# AC_DC_POWER.net
KiCad netlist of a schematic drawn in Altium Designer
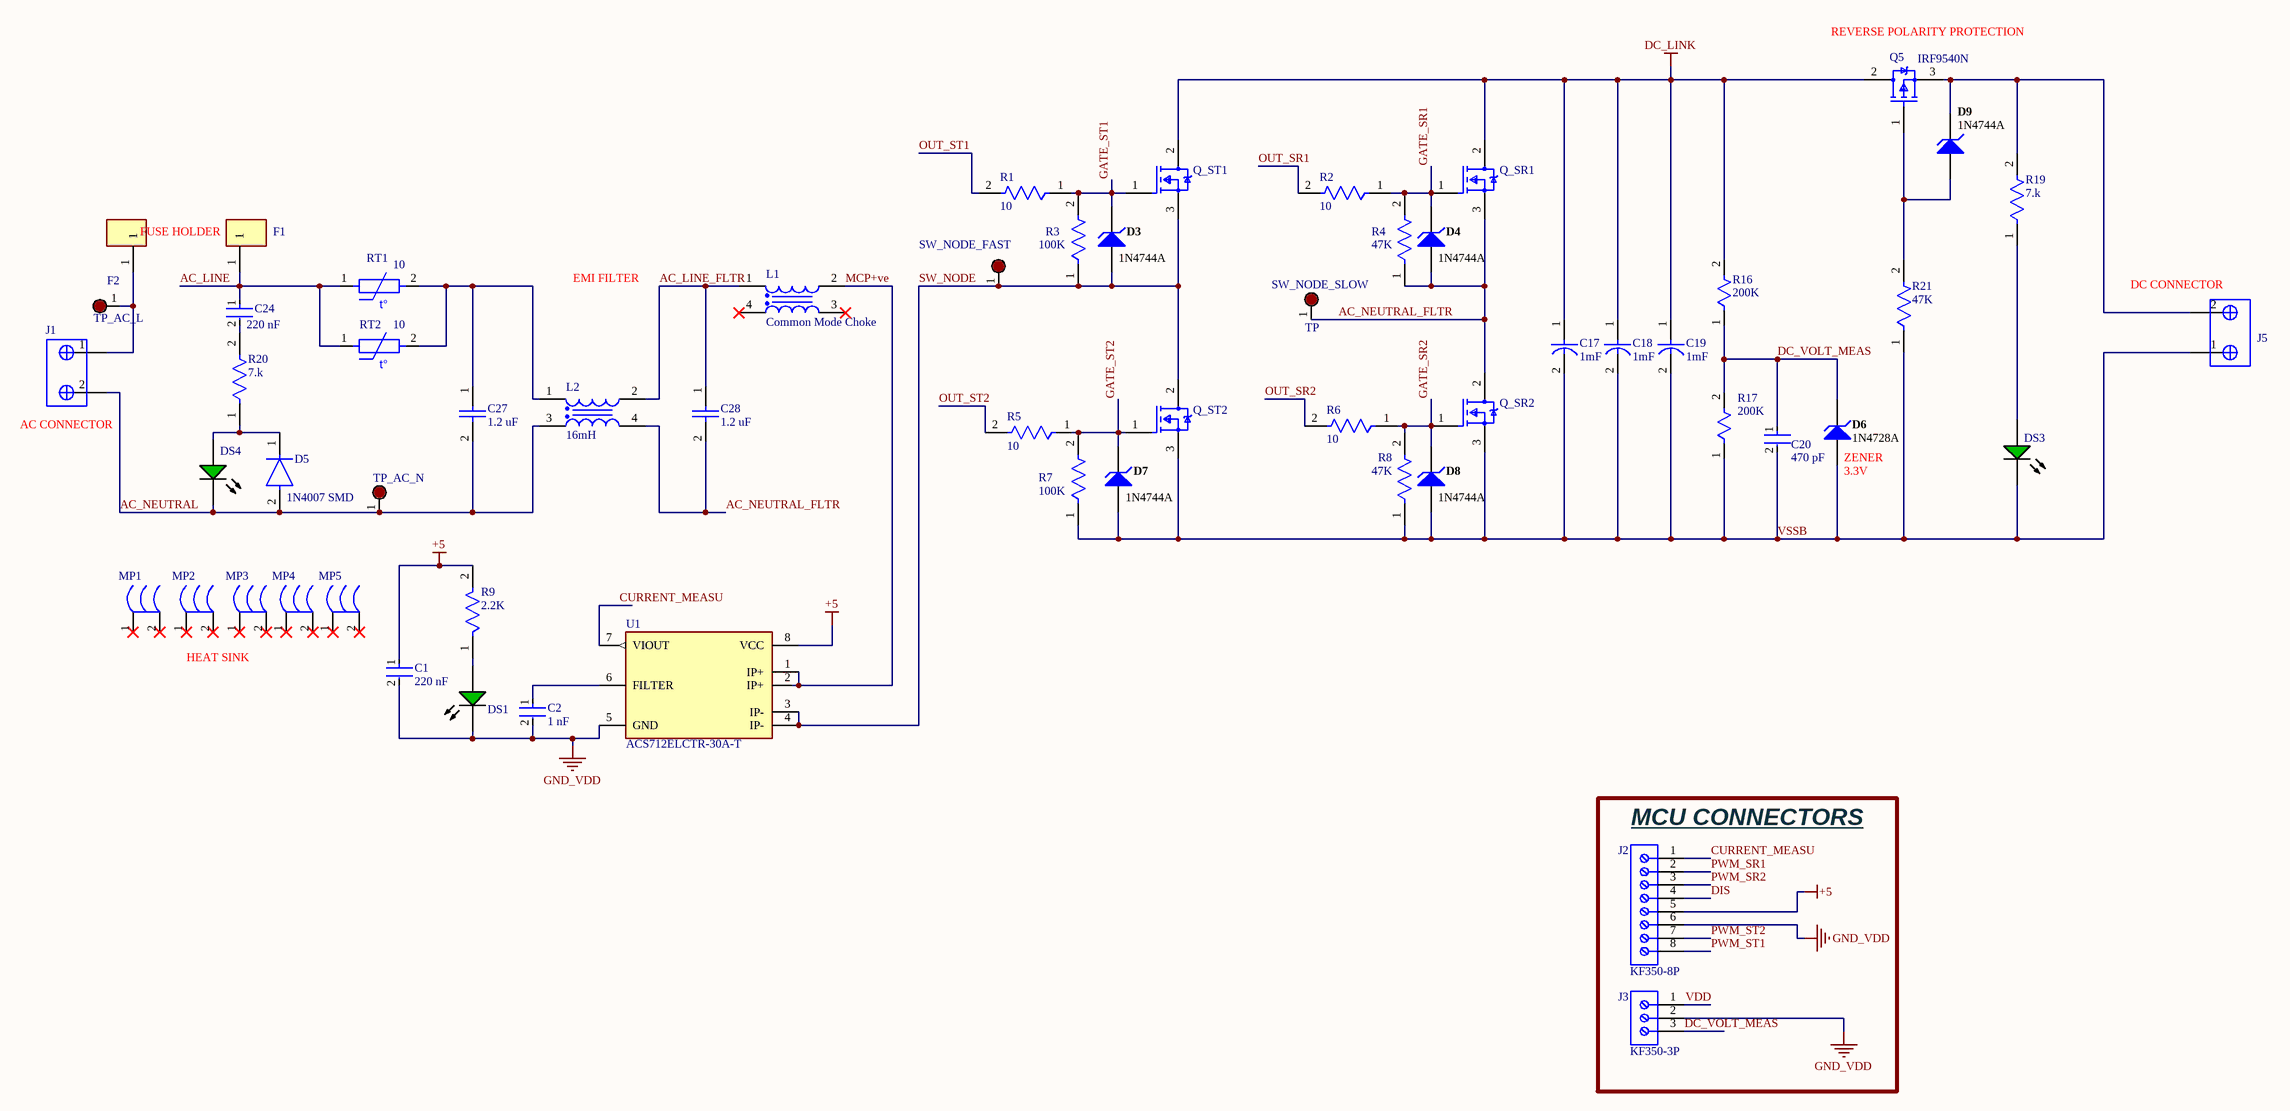
[diagram p0: AC_DC_POWER.SchDoc]

(export (version "E")
  (design (tool "Eeschema 10.0.6"))
  (components
    (comp (ref "C1")
      (value "220 nF")
      (footprint "FP-C0805C-DN-MFG")
      (description "CAP CER 0.22UF 50V X7R 0805")
      (fields
        (field (name "MANUFACTURER") "KEMET")
        (field (name "OCTOPART") "https://octopart.com/c0805c224k5ractu-kemet-144670")
      )
      (libsource (lib "Altium Content Vault") (part "b4654b650e69147ec39a6b967a45e02"))
    )
    (comp (ref "C2")
      (value "1 nF")
      (footprint "FP-C0805C-DN-MFG")
      (description "CAP CER 0.22UF 50V X7R 0805")
      (fields
        (field (name "MANUFACTURER") "KEMET")
        (field (name "OCTOPART") "https://octopart.com/c0805c224k5ractu-kemet-144670")
      )
      (libsource (lib "Altium Content Vault") (part "b4654b650e69147ec39a6b967a45e02"))
    )
    (comp (ref "C17")
      (value "1mF")
      (footprint "PCBComponent_1")
      (libsource (lib "CD293H Capacitor") (part "C"))
    )
    (comp (ref "C18")
      (value "1mF")
      (footprint "PCBComponent_1")
      (libsource (lib "CD293H Capacitor") (part "C"))
    )
    (comp (ref "C19")
      (value "1mF")
      (footprint "PCBComponent_1")
      (libsource (lib "CD293H Capacitor") (part "C"))
    )
    (comp (ref "C20")
      (value "470 pF")
      (footprint "FP-C0805C-DN-MFG")
      (description "CAP CER 0.22UF 50V X7R 0805")
      (fields
        (field (name "MANUFACTURER") "KEMET")
        (field (name "OCTOPART") "https://octopart.com/c0805c224k5ractu-kemet-144670")
      )
      (libsource (lib "Altium Content Vault") (part "b4654b650e69147ec39a6b967a45e02"))
    )
    (comp (ref "C24")
      (value "220 nF")
      (footprint "FP-C0805C-DN-MFG")
      (description "CAP CER 0.22UF 50V X7R 0805")
      (fields
        (field (name "MANUFACTURER") "KEMET")
        (field (name "OCTOPART") "https://octopart.com/c0805c224k5ractu-kemet-144670")
      )
      (libsource (lib "Altium Content Vault") (part "b4654b650e69147ec39a6b967a45e02"))
    )
    (comp (ref "C27")
      (value "1.2 uF")
      (footprint "PCBComponent_1")
      (description "H124K \r\n450MPPN")
      (libsource (lib "H124K Film Capacitor") (part "H124K"))
    )
    (comp (ref "C28")
      (value "1.2 uF")
      (footprint "PCBComponent_1")
      (description "H124K \r\n450MPPN")
      (libsource (lib "H124K Film Capacitor") (part "H124K"))
    )
    (comp (ref "D3")
      (value "1N4744A")
      (footprint "FAIR-DO-41-2_V")
      (description "Zener Diode, 15V, 1W, 5%, -65 to 200 degC, 2-Pin DO-41, Body 2.72 x 5.2 mm, RoHS")
      (fields (field (name "MANUFACTURER") "Fairchild Semiconductor") (field (name "TOLERANCE") "5%"))
      (libsource (lib "Altium Content Vault") (part "FAIR-DZEN-A1K2-2"))
    )
    (comp (ref "D4")
      (value "1N4744A")
      (footprint "FAIR-DO-41-2_V")
      (description "Zener Diode, 15V, 1W, 5%, -65 to 200 degC, 2-Pin DO-41, Body 2.72 x 5.2 mm, RoHS")
      (fields (field (name "MANUFACTURER") "Fairchild Semiconductor") (field (name "TOLERANCE") "5%"))
      (libsource (lib "Altium Content Vault") (part "FAIR-DZEN-A1K2-2"))
    )
    (comp (ref "D5")
      (value "1N4007 SMD")
      (footprint "FP-1N4007_SMD-IPC_C")
      (description "Rectifier, 1Kv, 1A, Do-214Ac Rohs Compliant: Yes")
      (libsource (lib "Altium Content Vault") (part "d7152d700b627762746794eb795d46e"))
    )
    (comp (ref "D6")
      (value "1N4728A")
      (footprint "FAIR-DO-41-2_V")
      (description "Zener Diode, 3.3V, 1W, 5%, -65 to 200 degC, 2-Pin DO-41, Body 2.72 x 5.2 mm, RoHS")
      (fields (field (name "MANUFACTURER") "Fairchild Semiconductor") (field (name "TOLERANCE") "5%"))
      (libsource (lib "Altium Content Vault") (part "FAIR-DZEN-A1K2-2"))
    )
    (comp (ref "D7")
      (value "1N4744A")
      (footprint "FAIR-DO-41-2_V")
      (description "Zener Diode, 15V, 1W, 5%, -65 to 200 degC, 2-Pin DO-41, Body 2.72 x 5.2 mm, RoHS")
      (fields (field (name "MANUFACTURER") "Fairchild Semiconductor") (field (name "TOLERANCE") "5%"))
      (libsource (lib "Altium Content Vault") (part "FAIR-DZEN-A1K2-2"))
    )
    (comp (ref "D8")
      (value "1N4744A")
      (footprint "FAIR-DO-41-2_V")
      (description "Zener Diode, 15V, 1W, 5%, -65 to 200 degC, 2-Pin DO-41, Body 2.72 x 5.2 mm, RoHS")
      (fields (field (name "MANUFACTURER") "Fairchild Semiconductor") (field (name "TOLERANCE") "5%"))
      (libsource (lib "Altium Content Vault") (part "FAIR-DZEN-A1K2-2"))
    )
    (comp (ref "D9")
      (value "1N4744A")
      (footprint "FAIR-DO-41-2_V")
      (description "Zener Diode, 15V, 1W, 5%, -65 to 200 degC, 2-Pin DO-41, Body 2.72 x 5.2 mm, RoHS")
      (fields (field (name "MANUFACTURER") "Fairchild Semiconductor") (field (name "TOLERANCE") "5%"))
      (libsource (lib "Altium Content Vault") (part "FAIR-DZEN-A1K2-2"))
    )
    (comp (ref "DS1")
      (value "HSMG-C170")
      (footprint "AVAG-HSMX-C170_V")
      (description "Chip LED, Green, 2.2 V, -40 to 85 degC, 2-Pin SMD, Pb-Free, Tape and Reel")
      (fields (field (name "MANUFACTURER") "Avago"))
      (libsource (lib "Altium Content Vault") (part "LED_GREEN_A1K2-2"))
    )
    (comp (ref "DS3")
      (value "HSMG-C170")
      (footprint "AVAG-HSMX-C170_V")
      (description "Chip LED, Green, 2.2 V, -40 to 85 degC, 2-Pin SMD, Pb-Free, Tape and Reel")
      (fields (field (name "MANUFACTURER") "Avago"))
      (libsource (lib "Altium Content Vault") (part "LED_GREEN_A1K2-2"))
    )
    (comp (ref "DS4")
      (value "HSMG-C170")
      (footprint "AVAG-HSMX-C170_V")
      (description "Chip LED, Green, 2.2 V, -40 to 85 degC, 2-Pin SMD, Pb-Free, Tape and Reel")
      (fields (field (name "MANUFACTURER") "Avago"))
      (libsource (lib "Altium Content Vault") (part "LED_GREEN_A1K2-2"))
    )
    (comp (ref "F1")
      (value "0751.0110")
      (footprint "FP-0751_0110-MFG")
      (description "FUSE CLIP CARTRIDGE 10A PCB")
      (fields
        (field (name "OCTOPART") "https://octopart.com/0751.0110-schurter-19402")
        (field (name "MANUFACTURER") "Schurter")
      )
      (libsource (lib "") (part "6594cd1380bf084bed0a40489f8b218_1"))
    )
    (comp (ref "F2")
      (value "0751.0110")
      (footprint "FP-0751_0110-MFG")
      (description "FUSE CLIP CARTRIDGE 10A PCB")
      (fields
        (field (name "OCTOPART") "https://octopart.com/0751.0110-schurter-19402")
        (field (name "MANUFACTURER") "Schurter")
      )
      (libsource (lib "Altium Content Vault") (part "6594cd1380bf084bed0a40489f8b218"))
    )
    (comp (ref "J1")
      (value "Barrier_2_pins")
      (footprint "PCBComponent_1")
      (libsource (lib "Barrier Terminal 9.5mm 2-Pins") (part "Barrier_2_pins"))
    )
    (comp (ref "J2")
      (value "KF350-8P")
      (footprint "PCBComponent_1")
      (libsource (lib "KF350-3.5mm-8P") (part "KF350-8P"))
    )
    (comp (ref "J3")
      (value "KF350-3P")
      (footprint "PCBComponent_1")
      (libsource (lib "KF350-3P") (part "KF350-3P"))
    )
    (comp (ref "J5")
      (value "Barrier_2_pins")
      (footprint "PCBComponent_1")
      (libsource (lib "Barrier Terminal 9.5mm 2-Pins") (part "Barrier_2_pins"))
    )
    (comp (ref "L1")
      (value "Common Mode Choke")
      (footprint "PCBComponent_1")
      (libsource (lib "R6123-X425_Choke") (part "T60405-R6123-X425"))
    )
    (comp (ref "L2")
      (value "16mH")
      (footprint "PCBComponent_1")
      (description "Common Mode Choke\r\nEach Coil inductance = 16mH")
      (libsource (lib "Common Mode Choke") (part "Choke"))
    )
    (comp (ref "MP1")
      (value "Heat Sink")
      (footprint "PCBComponent_1")
      (libsource (lib "Heat Sink 34_12_25") (part "Heat Sink"))
    )
    (comp (ref "MP2")
      (value "Heat Sink")
      (footprint "PCBComponent_1")
      (libsource (lib "Heat Sink 34_12_25") (part "Heat Sink"))
    )
    (comp (ref "MP3")
      (value "Heat Sink")
      (footprint "PCBComponent_1")
      (libsource (lib "Heat Sink 34_12_25") (part "Heat Sink"))
    )
    (comp (ref "MP4")
      (value "Heat Sink")
      (footprint "PCBComponent_1")
      (libsource (lib "Heat Sink 34_12_25") (part "Heat Sink"))
    )
    (comp (ref "MP5")
      (value "Heat Sink")
      (footprint "PCBComponent_1")
      (libsource (lib "Heat Sink 34_12_25") (part "Heat Sink"))
    )
    (comp (ref "Q5")
      (value "IRF9540N")
      (footprint "PCBComponent_1")
      (libsource (lib "IRF9540N") (part "IRF9540N"))
    )
    (comp (ref "Q_SR1")
      (value "IRFP4227PBF")
      (footprint "FP-PG-TO247-3-MFG")
      (description "MOSFET N-CH 200V 65A TO247AC")
      (libsource (lib "Altium Content Vault") (part "8b62d417cbef8344eebe0bde0c45977"))
    )
    (comp (ref "Q_SR2")
      (value "IRFP4227PBF")
      (footprint "FP-PG-TO247-3-MFG")
      (description "MOSFET N-CH 200V 65A TO247AC")
      (libsource (lib "Altium Content Vault") (part "8b62d417cbef8344eebe0bde0c45977"))
    )
    (comp (ref "Q_ST1")
      (value "IRFP4227PBF")
      (footprint "FP-PG-TO247-3-MFG")
      (description "MOSFET N-CH 200V 65A TO247AC")
      (libsource (lib "Altium Content Vault") (part "8b62d417cbef8344eebe0bde0c45977"))
    )
    (comp (ref "Q_ST2")
      (value "IRFP4227PBF")
      (footprint "FP-PG-TO247-3-MFG")
      (description "MOSFET N-CH 200V 65A TO247AC")
      (libsource (lib "Altium Content Vault") (part "8b62d417cbef8344eebe0bde0c45977"))
    )
    (comp (ref "R1")
      (value "10")
      (footprint "FP-RC0805-0_6-IPC_C")
      (description "RES 100K OHM 1% 1/8W 0805")
      (fields (field (name "TOLERANCE") "1%"))
      (libsource (lib "Altium Content Vault") (part "1029c3af85768c4190bb7ad29bc67b5"))
    )
    (comp (ref "R2")
      (value "10")
      (footprint "FP-RC0805-0_6-IPC_C")
      (description "RES 100K OHM 1% 1/8W 0805")
      (fields (field (name "TOLERANCE") "1%"))
      (libsource (lib "Altium Content Vault") (part "1029c3af85768c4190bb7ad29bc67b5"))
    )
    (comp (ref "R3")
      (value "100K")
      (footprint "FP-RC0805-0_6-IPC_C")
      (description "RES 100K OHM 1% 1/8W 0805")
      (fields (field (name "TOLERANCE") "1%"))
      (libsource (lib "Altium Content Vault") (part "1029c3af85768c4190bb7ad29bc67b5"))
    )
    (comp (ref "R4")
      (value "47K")
      (footprint "FP-RC0805-0_6-IPC_C")
      (description "RES 100K OHM 1% 1/8W 0805")
      (fields (field (name "TOLERANCE") "1%"))
      (libsource (lib "Altium Content Vault") (part "1029c3af85768c4190bb7ad29bc67b5"))
    )
    (comp (ref "R5")
      (value "10")
      (footprint "FP-RC0805-0_6-IPC_C")
      (description "RES 100K OHM 1% 1/8W 0805")
      (fields (field (name "TOLERANCE") "1%"))
      (libsource (lib "Altium Content Vault") (part "1029c3af85768c4190bb7ad29bc67b5"))
    )
    (comp (ref "R6")
      (value "10")
      (footprint "FP-RC0805-0_6-IPC_C")
      (description "RES 100K OHM 1% 1/8W 0805")
      (fields (field (name "TOLERANCE") "1%"))
      (libsource (lib "Altium Content Vault") (part "1029c3af85768c4190bb7ad29bc67b5"))
    )
    (comp (ref "R7")
      (value "100K")
      (footprint "FP-RC0805-0_6-IPC_C")
      (description "RES 100K OHM 1% 1/8W 0805")
      (fields (field (name "TOLERANCE") "1%"))
      (libsource (lib "Altium Content Vault") (part "1029c3af85768c4190bb7ad29bc67b5"))
    )
    (comp (ref "R8")
      (value "47K")
      (footprint "FP-RC0805-0_6-IPC_C")
      (description "RES 100K OHM 1% 1/8W 0805")
      (fields (field (name "TOLERANCE") "1%"))
      (libsource (lib "Altium Content Vault") (part "1029c3af85768c4190bb7ad29bc67b5"))
    )
    (comp (ref "R9")
      (value "2.2K")
      (footprint "FP-RC0805-0_6-IPC_C")
      (description "RES 100K OHM 1% 1/8W 0805")
      (fields (field (name "TOLERANCE") "1%"))
      (libsource (lib "Altium Content Vault") (part "1029c3af85768c4190bb7ad29bc67b5"))
    )
    (comp (ref "R16")
      (value "200K")
      (footprint "PCBComponent_1")
      (libsource (lib "RES_0.125W_AXIAL") (part "RES"))
    )
    (comp (ref "R17")
      (value "200K")
      (footprint "PCBComponent_1")
      (libsource (lib "RES_0.125W_AXIAL") (part "RES"))
    )
    (comp (ref "R19")
      (value "7.k")
      (footprint "FP-RC0805-0_6-IPC_C")
      (description "RES 100K OHM 1% 1/8W 0805")
      (fields (field (name "TOLERANCE") "1%"))
      (libsource (lib "Altium Content Vault") (part "1029c3af85768c4190bb7ad29bc67b5"))
    )
    (comp (ref "R20")
      (value "7.k")
      (footprint "FP-RC0805-0_6-IPC_C")
      (description "RES 100K OHM 1% 1/8W 0805")
      (fields (field (name "TOLERANCE") "1%"))
      (libsource (lib "Altium Content Vault") (part "1029c3af85768c4190bb7ad29bc67b5"))
    )
    (comp (ref "R21")
      (value "47K")
      (footprint "FP-RC0805-0_6-IPC_C")
      (description "RES 47K OHM 1% 1/8W 0805")
      (fields (field (name "TOLERANCE") "1%"))
      (libsource (lib "Altium Content Vault") (part "1029c3af85768c4190bb7ad29bc67b5"))
    )
    (comp (ref "RT1")
      (value "10")
      (footprint "PCBComponent_1")
      (description "10Ω 7A 7.5W ±20% 3200K ±10% Plugin,P=10mm NTC Thermistors ROHS")
      (libsource (lib "NTC 10-D25 Thermistor") (part "NTC 10-D25"))
    )
    (comp (ref "RT2")
      (value "10")
      (footprint "PCBComponent_1")
      (description "10Ω 7A 7.5W ±20% 3200K ±10% Plugin,P=10mm NTC Thermistors ROHS")
      (libsource (lib "NTC 10-D25 Thermistor") (part "NTC 10-D25"))
    )
    (comp (ref "SW_NODE_FAST")
      (value "TP")
      (footprint "PCBComponent_1")
      (description "Test Point, Miniature, Red, TH")
      (libsource (lib "Test_Pin_RED") (part "TP"))
    )
    (comp (ref "SW_NODE_SLOW")
      (value "TP")
      (footprint "PCBComponent_1")
      (description "Test Point, Miniature, Red, TH")
      (libsource (lib "Test_Pin_RED") (part "TP"))
    )
    (comp (ref "TP_AC_L")
      (value "AC_LINE")
      (footprint "PCBComponent_1")
      (description "Test Point, Miniature, Red, TH")
      (libsource (lib "Test_Pin_RED") (part "TP"))
    )
    (comp (ref "TP_AC_N")
      (value "AC_LINE")
      (footprint "PCBComponent_1")
      (description "Test Point, Miniature, Red, TH")
      (libsource (lib "Test_Pin_RED") (part "TP"))
    )
    (comp (ref "U1")
      (value "ACS712ELCTR-30A-T")
      (footprint "FP-LC-8-IPC_C")
      (description "SENSOR CURRENT HALL 30A AC/DC")
      (libsource (lib "Altium Content Vault") (part "a0faa98973ef06dd62ff869f1199b2d"))
    )
  )
  (nets
    (net (code "1") (name "+5") (class "Default")
      (node (ref "C1") (pin "1") (pinfunction "1_1") (pintype "passive"))
      (node (ref "J2") (pin "5") (pinfunction "5_5") (pintype "passive"))
      (node (ref "R9") (pin "2") (pinfunction "2_2") (pintype "passive"))
      (node (ref "U1") (pin "8") (pinfunction "VCC_8") (pintype "power_in"))
    )
    (net (code "2") (name "/AC_LINE") (class "Default")
      (node (ref "C24") (pin "1") (pinfunction "1_1") (pintype "passive"))
      (node (ref "F1") (pin "1") (pinfunction "1_1") (pintype "passive"))
      (node (ref "RT1") (pin "1") (pinfunction "1_1") (pintype "passive"))
      (node (ref "RT2") (pin "1") (pinfunction "1_1") (pintype "passive"))
    )
    (net (code "3") (name "/AC_LINE_FLTR") (class "Default")
      (node (ref "C28") (pin "1") (pinfunction "1_1") (pintype "passive"))
      (node (ref "L1") (pin "1") (pinfunction "1_1") (pintype "passive"))
      (node (ref "L2") (pin "2") (pinfunction "4_2") (pintype "passive"))
    )
    (net (code "4") (name "/AC_NEUTRAL") (class "Default")
      (node (ref "C27") (pin "2") (pinfunction "2_2") (pintype "passive"))
      (node (ref "D5") (pin "2") (pinfunction "A_2") (pintype "passive"))
      (node (ref "DS4") (pin "2") (pinfunction "K_2") (pintype "passive"))
      (node (ref "J1") (pin "2") (pinfunction "2_2") (pintype "passive"))
      (node (ref "L2") (pin "3") (pinfunction "2_3") (pintype "passive"))
      (node (ref "TP_AC_N") (pin "1") (pinfunction "1_1") (pintype "passive"))
    )
    (net (code "5") (name "/AC_NEUTRAL_FLTR") (class "Default")
      (node (ref "C28") (pin "2") (pinfunction "2_2") (pintype "passive"))
      (node (ref "D4") (pin "1") (pinfunction "A_1") (pintype "passive"))
      (node (ref "L2") (pin "4") (pinfunction "3_4") (pintype "passive"))
      (node (ref "Q_SR1") (pin "3") (pinfunction "SOURCE_3") (pintype "passive"))
      (node (ref "Q_SR2") (pin "2") (pinfunction "DRAIN_2") (pintype "passive"))
      (node (ref "R4") (pin "1") (pinfunction "1_1") (pintype "passive"))
      (node (ref "SW_NODE_SLOW") (pin "1") (pinfunction "1_1") (pintype "passive"))
    )
    (net (code "6") (name "/CURRENT_MEASU") (class "Default")
      (node (ref "J2") (pin "1") (pinfunction "1_1") (pintype "passive"))
      (node (ref "U1") (pin "7") (pinfunction "VIOUT_7") (pintype "output"))
    )
    (net (code "7") (name "/DC_VOLT_MEAS") (class "Default")
      (node (ref "C20") (pin "1") (pinfunction "1_1") (pintype "passive"))
      (node (ref "D6") (pin "2") (pinfunction "K_2") (pintype "passive"))
      (node (ref "J3") (pin "3") (pinfunction "3_3") (pintype "passive"))
      (node (ref "R16") (pin "1") (pinfunction "1_1") (pintype "passive"))
      (node (ref "R17") (pin "2") (pinfunction "2_2") (pintype "passive"))
    )
    (net (code "8") (name "/DIS") (class "Default")
      (node (ref "J2") (pin "4") (pinfunction "4_4") (pintype "passive"))
    )
    (net (code "9") (name "/GATE_SR1") (class "Default")
      (node (ref "D4") (pin "2") (pinfunction "K_2") (pintype "passive"))
      (node (ref "Q_SR1") (pin "1") (pinfunction "GATE_1") (pintype "passive"))
      (node (ref "R2") (pin "1") (pinfunction "1_1") (pintype "passive"))
      (node (ref "R4") (pin "2") (pinfunction "2_2") (pintype "passive"))
    )
    (net (code "10") (name "/GATE_SR2") (class "Default")
      (node (ref "D8") (pin "2") (pinfunction "K_2") (pintype "passive"))
      (node (ref "Q_SR2") (pin "1") (pinfunction "GATE_1") (pintype "passive"))
      (node (ref "R6") (pin "1") (pinfunction "1_1") (pintype "passive"))
      (node (ref "R8") (pin "2") (pinfunction "2_2") (pintype "passive"))
    )
    (net (code "11") (name "/GATE_ST1") (class "Default")
      (node (ref "D3") (pin "2") (pinfunction "K_2") (pintype "passive"))
      (node (ref "Q_ST1") (pin "1") (pinfunction "GATE_1") (pintype "passive"))
      (node (ref "R1") (pin "1") (pinfunction "1_1") (pintype "passive"))
      (node (ref "R3") (pin "2") (pinfunction "2_2") (pintype "passive"))
    )
    (net (code "12") (name "/GATE_ST2") (class "Default")
      (node (ref "D7") (pin "2") (pinfunction "K_2") (pintype "passive"))
      (node (ref "Q_ST2") (pin "1") (pinfunction "GATE_1") (pintype "passive"))
      (node (ref "R5") (pin "1") (pinfunction "1_1") (pintype "passive"))
      (node (ref "R7") (pin "2") (pinfunction "2_2") (pintype "passive"))
    )
    (net (code "13") (name "/MCP+ve") (class "Default")
      (node (ref "L1") (pin "2") (pinfunction "4_2") (pintype "passive"))
      (node (ref "U1") (pin "1") (pinfunction "IP+_1") (pintype "passive"))
      (node (ref "U1") (pin "2") (pinfunction "IP+_2") (pintype "passive"))
    )
    (net (code "14") (name "/OUT_SR1") (class "Default")
      (node (ref "R2") (pin "2") (pinfunction "2_2") (pintype "passive"))
    )
    (net (code "15") (name "/OUT_SR2") (class "Default")
      (node (ref "R6") (pin "2") (pinfunction "2_2") (pintype "passive"))
    )
    (net (code "16") (name "/OUT_ST1") (class "Default")
      (node (ref "R1") (pin "2") (pinfunction "2_2") (pintype "passive"))
    )
    (net (code "17") (name "/OUT_ST2") (class "Default")
      (node (ref "R5") (pin "2") (pinfunction "2_2") (pintype "passive"))
    )
    (net (code "18") (name "/PWM_SR1") (class "Default")
      (node (ref "J2") (pin "2") (pinfunction "2_2") (pintype "passive"))
    )
    (net (code "19") (name "/PWM_SR2") (class "Default")
      (node (ref "J2") (pin "3") (pinfunction "3_3") (pintype "passive"))
    )
    (net (code "20") (name "/PWM_ST1") (class "Default")
      (node (ref "J2") (pin "8") (pinfunction "8_8") (pintype "passive"))
    )
    (net (code "21") (name "/PWM_ST2") (class "Default")
      (node (ref "J2") (pin "7") (pinfunction "7_7") (pintype "passive"))
    )
    (net (code "22") (name "/SW_NODE") (class "Default")
      (node (ref "D3") (pin "1") (pinfunction "A_1") (pintype "passive"))
      (node (ref "Q_ST1") (pin "3") (pinfunction "SOURCE_3") (pintype "passive"))
      (node (ref "Q_ST2") (pin "2") (pinfunction "DRAIN_2") (pintype "passive"))
      (node (ref "R3") (pin "1") (pinfunction "1_1") (pintype "passive"))
      (node (ref "SW_NODE_FAST") (pin "1") (pinfunction "1_1") (pintype "passive"))
      (node (ref "U1") (pin "3") (pinfunction "IP-_3") (pintype "passive"))
      (node (ref "U1") (pin "4") (pinfunction "IP-_4") (pintype "passive"))
    )
    (net (code "23") (name "/VDD") (class "Default")
      (node (ref "J3") (pin "1") (pinfunction "1_1") (pintype "passive"))
    )
    (net (code "24") (name "/VSSB") (class "Default")
      (node (ref "C17") (pin "2") (pinfunction "2_2") (pintype "passive"))
      (node (ref "C18") (pin "2") (pinfunction "2_2") (pintype "passive"))
      (node (ref "C19") (pin "2") (pinfunction "2_2") (pintype "passive"))
      (node (ref "C20") (pin "2") (pinfunction "2_2") (pintype "passive"))
      (node (ref "D6") (pin "1") (pinfunction "A_1") (pintype "passive"))
      (node (ref "D7") (pin "1") (pinfunction "A_1") (pintype "passive"))
      (node (ref "D8") (pin "1") (pinfunction "A_1") (pintype "passive"))
      (node (ref "DS3") (pin "2") (pinfunction "K_2") (pintype "passive"))
      (node (ref "J5") (pin "1") (pinfunction "1_1") (pintype "passive"))
      (node (ref "Q_SR2") (pin "3") (pinfunction "SOURCE_3") (pintype "passive"))
      (node (ref "Q_ST2") (pin "3") (pinfunction "SOURCE_3") (pintype "passive"))
      (node (ref "R17") (pin "1") (pinfunction "1_1") (pintype "passive"))
      (node (ref "R21") (pin "1") (pinfunction "1_1") (pintype "passive"))
      (node (ref "R7") (pin "1") (pinfunction "1_1") (pintype "passive"))
      (node (ref "R8") (pin "1") (pinfunction "1_1") (pintype "passive"))
    )
    (net (code "25") (name "DC_LINK") (class "Default")
      (node (ref "C17") (pin "1") (pinfunction "1_1") (pintype "passive"))
      (node (ref "C18") (pin "1") (pinfunction "1_1") (pintype "passive"))
      (node (ref "C19") (pin "1") (pinfunction "1_1") (pintype "passive"))
      (node (ref "Q5") (pin "2") (pinfunction "Drain_2") (pintype "passive"))
      (node (ref "Q_SR1") (pin "2") (pinfunction "DRAIN_2") (pintype "passive"))
      (node (ref "Q_ST1") (pin "2") (pinfunction "DRAIN_2") (pintype "passive"))
      (node (ref "R16") (pin "2") (pinfunction "2_2") (pintype "passive"))
    )
    (net (code "26") (name "GND_VDD") (class "Default")
      (node (ref "C1") (pin "2") (pinfunction "2_2") (pintype "passive"))
      (node (ref "C2") (pin "2") (pinfunction "2_2") (pintype "passive"))
      (node (ref "DS1") (pin "2") (pinfunction "K_2") (pintype "passive"))
      (node (ref "J2") (pin "6") (pinfunction "6_6") (pintype "passive"))
      (node (ref "J3") (pin "2") (pinfunction "2_2") (pintype "passive"))
      (node (ref "U1") (pin "5") (pinfunction "GND_5") (pintype "power_in"))
    )
    (net (code "27") (name "Net-(C24-Pad2)") (class "Default")
      (node (ref "C24") (pin "2") (pinfunction "2_2") (pintype "passive"))
      (node (ref "R20") (pin "2") (pinfunction "2_2") (pintype "passive"))
    )
    (net (code "28") (name "Net-(C27-Pad1)") (class "Default")
      (node (ref "C27") (pin "1") (pinfunction "1_1") (pintype "passive"))
      (node (ref "L2") (pin "1") (pinfunction "1_1") (pintype "passive"))
      (node (ref "RT1") (pin "2") (pinfunction "2_2") (pintype "passive"))
      (node (ref "RT2") (pin "2") (pinfunction "2_2") (pintype "passive"))
    )
    (net (code "29") (name "Net-(D5-C)") (class "Default")
      (node (ref "D5") (pin "1") (pinfunction "C_1") (pintype "passive"))
      (node (ref "DS4") (pin "1") (pinfunction "A_1") (pintype "passive"))
      (node (ref "R20") (pin "1") (pinfunction "1_1") (pintype "passive"))
    )
    (net (code "30") (name "Net-(D9-A)") (class "Default")
      (node (ref "D9") (pin "1") (pinfunction "A_1") (pintype "passive"))
      (node (ref "Q5") (pin "1") (pinfunction "Gate_1") (pintype "passive"))
      (node (ref "R21") (pin "2") (pinfunction "2_2") (pintype "passive"))
    )
    (net (code "31") (name "Net-(D9-K)") (class "Default")
      (node (ref "D9") (pin "2") (pinfunction "K_2") (pintype "passive"))
      (node (ref "J5") (pin "2") (pinfunction "2_2") (pintype "passive"))
      (node (ref "Q5") (pin "3") (pinfunction "Source_3") (pintype "passive"))
      (node (ref "R19") (pin "2") (pinfunction "2_2") (pintype "passive"))
    )
    (net (code "32") (name "Net-(DS1-A)") (class "Default")
      (node (ref "DS1") (pin "1") (pinfunction "A_1") (pintype "passive"))
      (node (ref "R9") (pin "1") (pinfunction "1_1") (pintype "passive"))
    )
    (net (code "33") (name "Net-(DS3-A)") (class "Default")
      (node (ref "DS3") (pin "1") (pinfunction "A_1") (pintype "passive"))
      (node (ref "R19") (pin "1") (pinfunction "1_1") (pintype "passive"))
    )
    (net (code "34") (name "Net-(F2-Pad1)") (class "Default")
      (node (ref "F2") (pin "1") (pinfunction "1_1") (pintype "passive"))
      (node (ref "J1") (pin "1") (pinfunction "1_1") (pintype "passive"))
      (node (ref "TP_AC_L") (pin "1") (pinfunction "1_1") (pintype "passive"))
    )
    (net (code "35") (name "Net-(U1-FILTER)") (class "Default")
      (node (ref "C2") (pin "1") (pinfunction "1_1") (pintype "passive"))
      (node (ref "U1") (pin "6") (pinfunction "FILTER_6") (pintype "passive"))
    )
    (net (code "36") (name "unconnected-(L1-2-Pad4)") (class "Default")
      (node (ref "L1") (pin "4") (pinfunction "2_4") (pintype "passive+no_connect"))
    )
    (net (code "37") (name "unconnected-(L1-Pad3)") (class "Default")
      (node (ref "L1") (pin "3") (pinfunction "3_3") (pintype "passive+no_connect"))
    )
    (net (code "38") (name "unconnected-(MP1-Pad1)") (class "Default")
      (node (ref "MP1") (pin "1") (pinfunction "1_1") (pintype "passive+no_connect"))
    )
    (net (code "39") (name "unconnected-(MP1-Pad2)") (class "Default")
      (node (ref "MP1") (pin "2") (pinfunction "2_2") (pintype "passive+no_connect"))
    )
    (net (code "40") (name "unconnected-(MP2-Pad1)") (class "Default")
      (node (ref "MP2") (pin "1") (pinfunction "1_1") (pintype "passive+no_connect"))
    )
    (net (code "41") (name "unconnected-(MP2-Pad2)") (class "Default")
      (node (ref "MP2") (pin "2") (pinfunction "2_2") (pintype "passive+no_connect"))
    )
    (net (code "42") (name "unconnected-(MP3-Pad1)") (class "Default")
      (node (ref "MP3") (pin "1") (pinfunction "1_1") (pintype "passive+no_connect"))
    )
    (net (code "43") (name "unconnected-(MP3-Pad2)") (class "Default")
      (node (ref "MP3") (pin "2") (pinfunction "2_2") (pintype "passive+no_connect"))
    )
    (net (code "44") (name "unconnected-(MP4-Pad1)") (class "Default")
      (node (ref "MP4") (pin "1") (pinfunction "1_1") (pintype "passive+no_connect"))
    )
    (net (code "45") (name "unconnected-(MP4-Pad2)") (class "Default")
      (node (ref "MP4") (pin "2") (pinfunction "2_2") (pintype "passive+no_connect"))
    )
    (net (code "46") (name "unconnected-(MP5-Pad1)") (class "Default")
      (node (ref "MP5") (pin "1") (pinfunction "1_1") (pintype "passive+no_connect"))
    )
    (net (code "47") (name "unconnected-(MP5-Pad2)") (class "Default")
      (node (ref "MP5") (pin "2") (pinfunction "2_2") (pintype "passive+no_connect"))
    )
  )
)
